# resistor-board.net
KiCad netlist of a schematic drawn in EAGLE
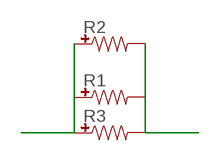
[diagram p0: schematic, sheet 1]

(export (version "E")
  (design (tool "Eeschema 10.0.6"))
  (components
    (comp (ref "R1")
      (value "RESISTORUNIVERSAL")
      (footprint "eagle-import:0402-0603-0805-UNIVERSAL")
      (libsource (lib "eagle-import") (part "RESISTORUNIVERSAL"))
    )
    (comp (ref "R2")
      (value "RESISTORAXIAL-0.3")
      (footprint "eagle-import:AXIAL-0.3")
      (libsource (lib "eagle-import") (part "RESISTORAXIAL-0.3"))
    )
    (comp (ref "R3")
      (value "RESISTOR1206")
      (footprint "eagle-import:1206")
      (libsource (lib "eagle-import") (part "RESISTOR1206"))
    )
  )
  (nets
    (net (code "1") (name "Net-(R1-1)") (class "Default")
      (node (ref "R1") (pin "+") (pinfunction "1_+") (pintype "passive"))
      (node (ref "R2") (pin "P$1") (pinfunction "1_P$1") (pintype "passive"))
      (node (ref "R3") (pin "1") (pinfunction "1_1") (pintype "passive"))
    )
    (net (code "2") (name "Net-(R1-2)") (class "Default")
      (node (ref "R1") (pin "-") (pinfunction "2_-") (pintype "passive"))
      (node (ref "R2") (pin "P$2") (pinfunction "2_P$2") (pintype "passive"))
      (node (ref "R3") (pin "2") (pinfunction "2_2") (pintype "passive"))
    )
  )
)
